# BPSU_1_5.net
KiCad netlist of a schematic drawn in EAGLE
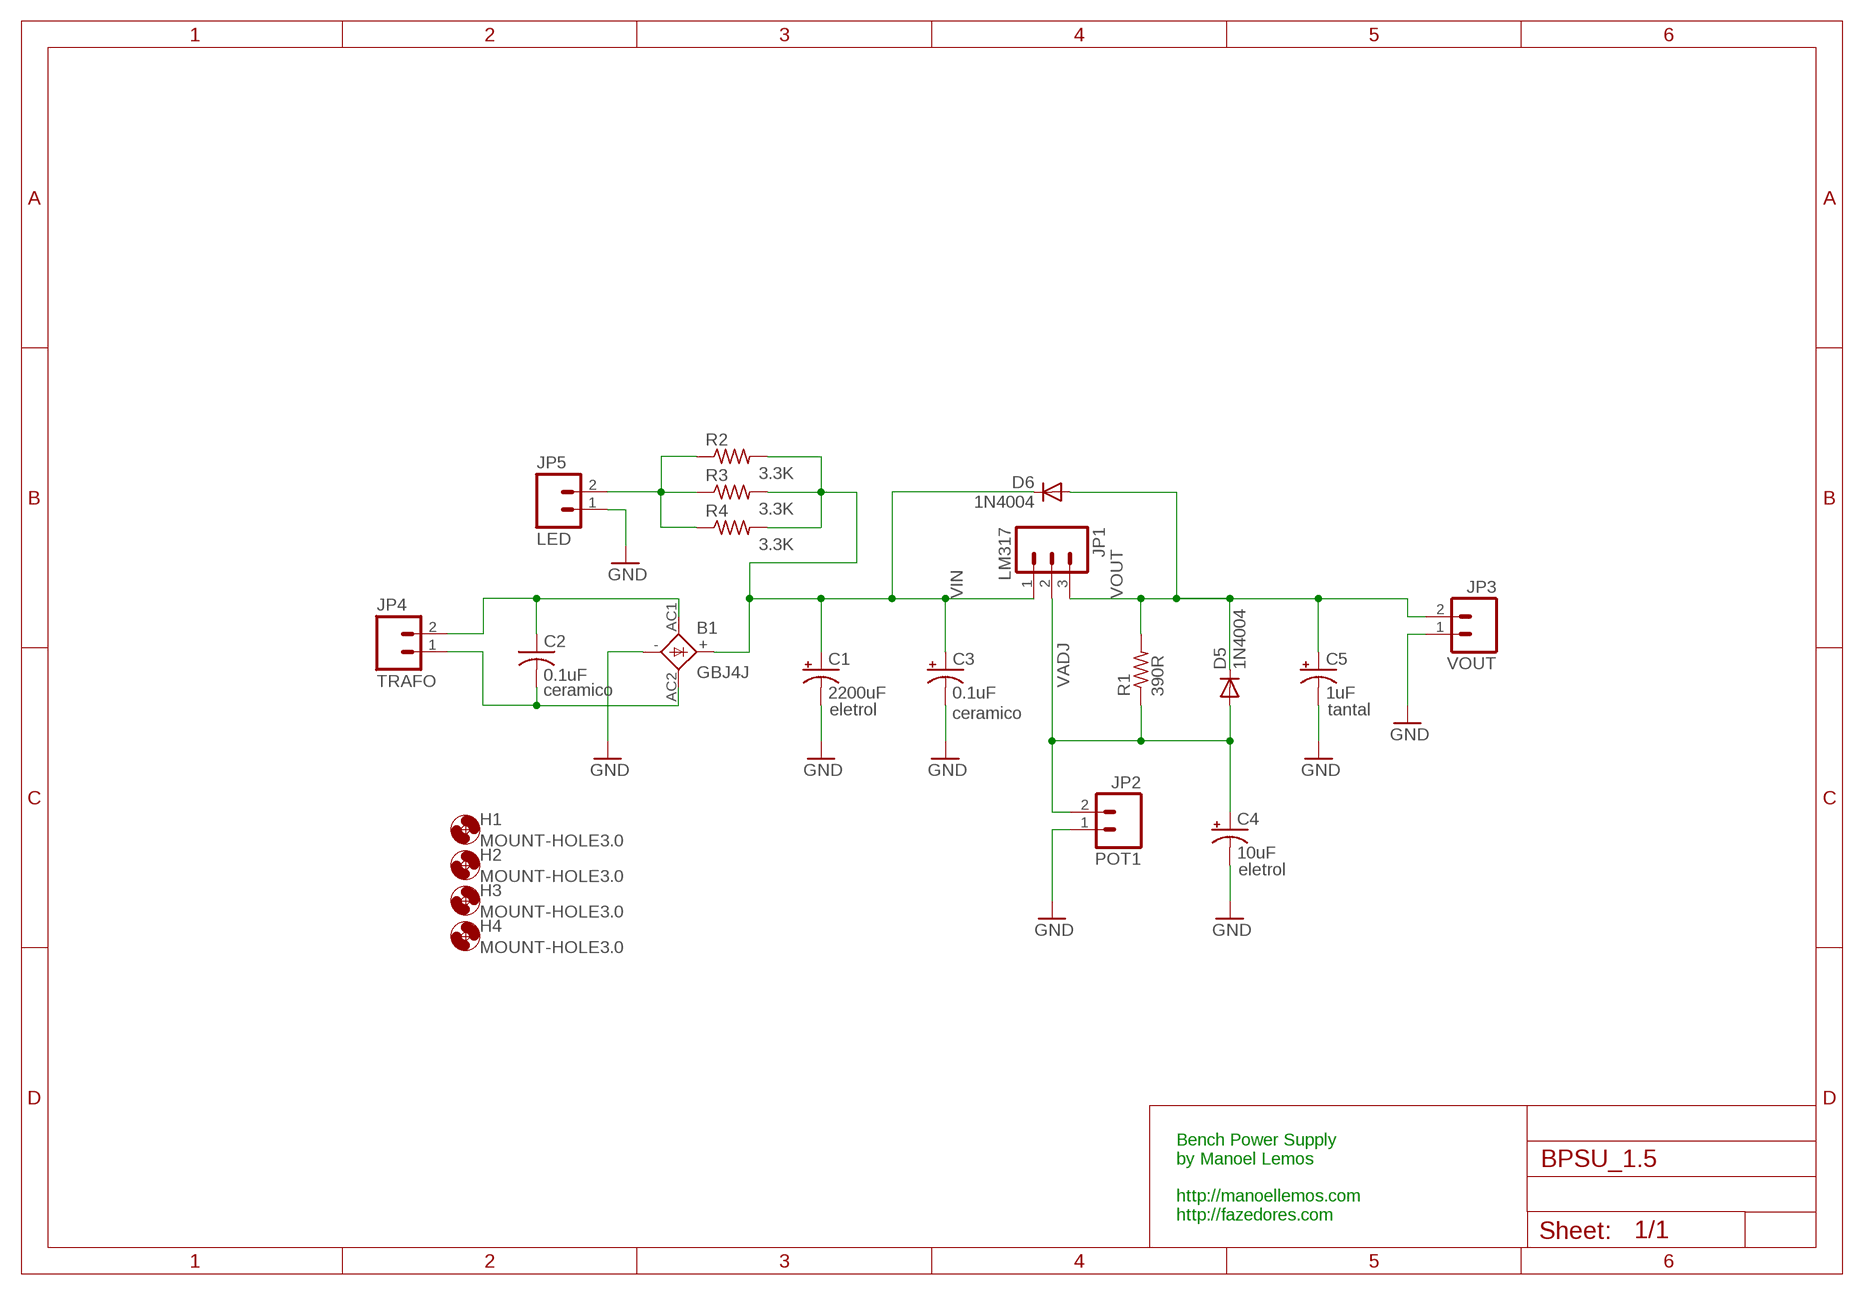
[diagram p0: schematic, sheet 1]

(export (version "E")
  (design (tool "Eeschema 10.0.6"))
  (components
    (comp (ref "B1")
      (value "GBJ4J")
      (footprint "eagle-import:GBJ")
      (libsource (lib "eagle-import") (part "GBJ4J"))
    )
    (comp (ref "C1")
      (value "2200uF")
      (footprint "eagle-import:E7,5-18")
      (libsource (lib "eagle-import") (part "CPOL-USE7.5-18"))
    )
    (comp (ref "C2")
      (value "0.1uF")
      (footprint "eagle-import:C075-063X106")
      (libsource (lib "eagle-import") (part "C-US075-063X106"))
    )
    (comp (ref "C3")
      (value "0.1uF")
      (footprint "eagle-import:E3,5-8")
      (libsource (lib "eagle-import") (part "CPOL-USE3.5-8"))
    )
    (comp (ref "C4")
      (value "10uF")
      (footprint "eagle-import:E3,5-8")
      (libsource (lib "eagle-import") (part "CPOL-USE3.5-8"))
    )
    (comp (ref "C5")
      (value "1uF")
      (footprint "eagle-import:E3,5-8")
      (libsource (lib "eagle-import") (part "CPOL-USE3.5-8"))
    )
    (comp (ref "D5")
      (value "1N4004")
      (footprint "eagle-import:DO41-10")
      (libsource (lib "eagle-import") (part "1N4004"))
    )
    (comp (ref "D6")
      (value "1N4004")
      (footprint "eagle-import:DO41-10")
      (libsource (lib "eagle-import") (part "1N4004"))
    )
    (comp (ref "H1")
      (value "MOUNT-HOLE3.0")
      (footprint "eagle-import:3,0")
      (libsource (lib "eagle-import") (part "MOUNT-HOLE3.0"))
    )
    (comp (ref "H2")
      (value "MOUNT-HOLE3.0")
      (footprint "eagle-import:3,0")
      (libsource (lib "eagle-import") (part "MOUNT-HOLE3.0"))
    )
    (comp (ref "H3")
      (value "MOUNT-HOLE3.0")
      (footprint "eagle-import:3,0")
      (libsource (lib "eagle-import") (part "MOUNT-HOLE3.0"))
    )
    (comp (ref "H4")
      (value "MOUNT-HOLE3.0")
      (footprint "eagle-import:3,0")
      (libsource (lib "eagle-import") (part "MOUNT-HOLE3.0"))
    )
    (comp (ref "JP1")
      (value "LM317")
      (footprint "eagle-import:1X03_LONGPADS")
      (libsource (lib "eagle-import") (part "M03LONGPADS"))
    )
    (comp (ref "JP2")
      (value "POT1")
      (footprint "eagle-import:1X02_LONGPADS_ML")
      (libsource (lib "eagle-import") (part "M02"))
    )
    (comp (ref "JP3")
      (value "VOUT")
      (footprint "eagle-import:1X02_LONGPADS_ML")
      (libsource (lib "eagle-import") (part "M02"))
    )
    (comp (ref "JP4")
      (value "TRAFO")
      (footprint "eagle-import:1X02_LONGPADS_ML")
      (libsource (lib "eagle-import") (part "M02"))
    )
    (comp (ref "JP5")
      (value "LED")
      (footprint "eagle-import:1X02_LONGPADS_ML")
      (libsource (lib "eagle-import") (part "M02"))
    )
    (comp (ref "R1")
      (value "390R")
      (footprint "eagle-import:0204_7")
      (libsource (lib "eagle-import") (part "R-US_0204/7"))
    )
    (comp (ref "R2")
      (value "3.3K")
      (footprint "eagle-import:0204_7")
      (libsource (lib "eagle-import") (part "R-US_0204/7"))
    )
    (comp (ref "R3")
      (value "3.3K")
      (footprint "eagle-import:0204_7")
      (libsource (lib "eagle-import") (part "R-US_0204/7"))
    )
    (comp (ref "R4")
      (value "3.3K")
      (footprint "eagle-import:0204_7")
      (libsource (lib "eagle-import") (part "R-US_0204/7"))
    )
  )
  (nets
    (net (code "1") (name "/VADJ") (class "Default")
      (node (ref "C4") (pin "+") (pinfunction "+_+") (pintype "passive"))
      (node (ref "D5") (pin "A") (pinfunction "A_A") (pintype "passive"))
      (node (ref "JP1") (pin "2") (pinfunction "2_2") (pintype "passive"))
      (node (ref "JP2") (pin "2") (pinfunction "2_2") (pintype "passive"))
      (node (ref "R1") (pin "1") (pinfunction "1_1") (pintype "passive"))
    )
    (net (code "2") (name "/VIN") (class "Default")
      (node (ref "B1") (pin "+") (pinfunction "+_+") (pintype "passive"))
      (node (ref "C1") (pin "+") (pinfunction "+_+") (pintype "passive"))
      (node (ref "C3") (pin "+") (pinfunction "+_+") (pintype "passive"))
      (node (ref "D6") (pin "C") (pinfunction "C_C") (pintype "passive"))
      (node (ref "JP1") (pin "1") (pinfunction "1_1") (pintype "passive"))
      (node (ref "R2") (pin "2") (pinfunction "2_2") (pintype "passive"))
      (node (ref "R3") (pin "2") (pinfunction "2_2") (pintype "passive"))
      (node (ref "R4") (pin "2") (pinfunction "2_2") (pintype "passive"))
    )
    (net (code "3") (name "/VOUT") (class "Default")
      (node (ref "C5") (pin "+") (pinfunction "+_+") (pintype "passive"))
      (node (ref "D5") (pin "C") (pinfunction "C_C") (pintype "passive"))
      (node (ref "D6") (pin "A") (pinfunction "A_A") (pintype "passive"))
      (node (ref "JP1") (pin "3") (pinfunction "3_3") (pintype "passive"))
      (node (ref "JP3") (pin "2") (pinfunction "2_2") (pintype "passive"))
      (node (ref "R1") (pin "2") (pinfunction "2_2") (pintype "passive"))
    )
    (net (code "4") (name "GND") (class "Default")
      (node (ref "B1") (pin "-") (pinfunction "-_-") (pintype "passive"))
      (node (ref "C1") (pin "-") (pinfunction "-_-") (pintype "passive"))
      (node (ref "C3") (pin "-") (pinfunction "-_-") (pintype "passive"))
      (node (ref "C4") (pin "-") (pinfunction "-_-") (pintype "passive"))
      (node (ref "C5") (pin "-") (pinfunction "-_-") (pintype "passive"))
      (node (ref "JP2") (pin "1") (pinfunction "1_1") (pintype "passive"))
      (node (ref "JP3") (pin "1") (pinfunction "1_1") (pintype "passive"))
      (node (ref "JP5") (pin "1") (pinfunction "1_1") (pintype "passive"))
    )
    (net (code "5") (name "Net-(B1-PadAC1)") (class "Default")
      (node (ref "B1") (pin "AC1") (pinfunction "AC1_AC1") (pintype "passive"))
      (node (ref "C2") (pin "1") (pinfunction "1_1") (pintype "passive"))
      (node (ref "JP4") (pin "2") (pinfunction "2_2") (pintype "passive"))
    )
    (net (code "6") (name "Net-(B1-PadAC2)") (class "Default")
      (node (ref "B1") (pin "AC2") (pinfunction "AC2_AC2") (pintype "passive"))
      (node (ref "C2") (pin "2") (pinfunction "2_2") (pintype "passive"))
      (node (ref "JP4") (pin "1") (pinfunction "1_1") (pintype "passive"))
    )
    (net (code "7") (name "Net-(JP5-Pad2)") (class "Default")
      (node (ref "JP5") (pin "2") (pinfunction "2_2") (pintype "passive"))
      (node (ref "R2") (pin "1") (pinfunction "1_1") (pintype "passive"))
      (node (ref "R3") (pin "1") (pinfunction "1_1") (pintype "passive"))
      (node (ref "R4") (pin "1") (pinfunction "1_1") (pintype "passive"))
    )
  )
)
